# mLRS-E28-board01-v004.net
KiCad netlist of a schematic drawn in EAGLE
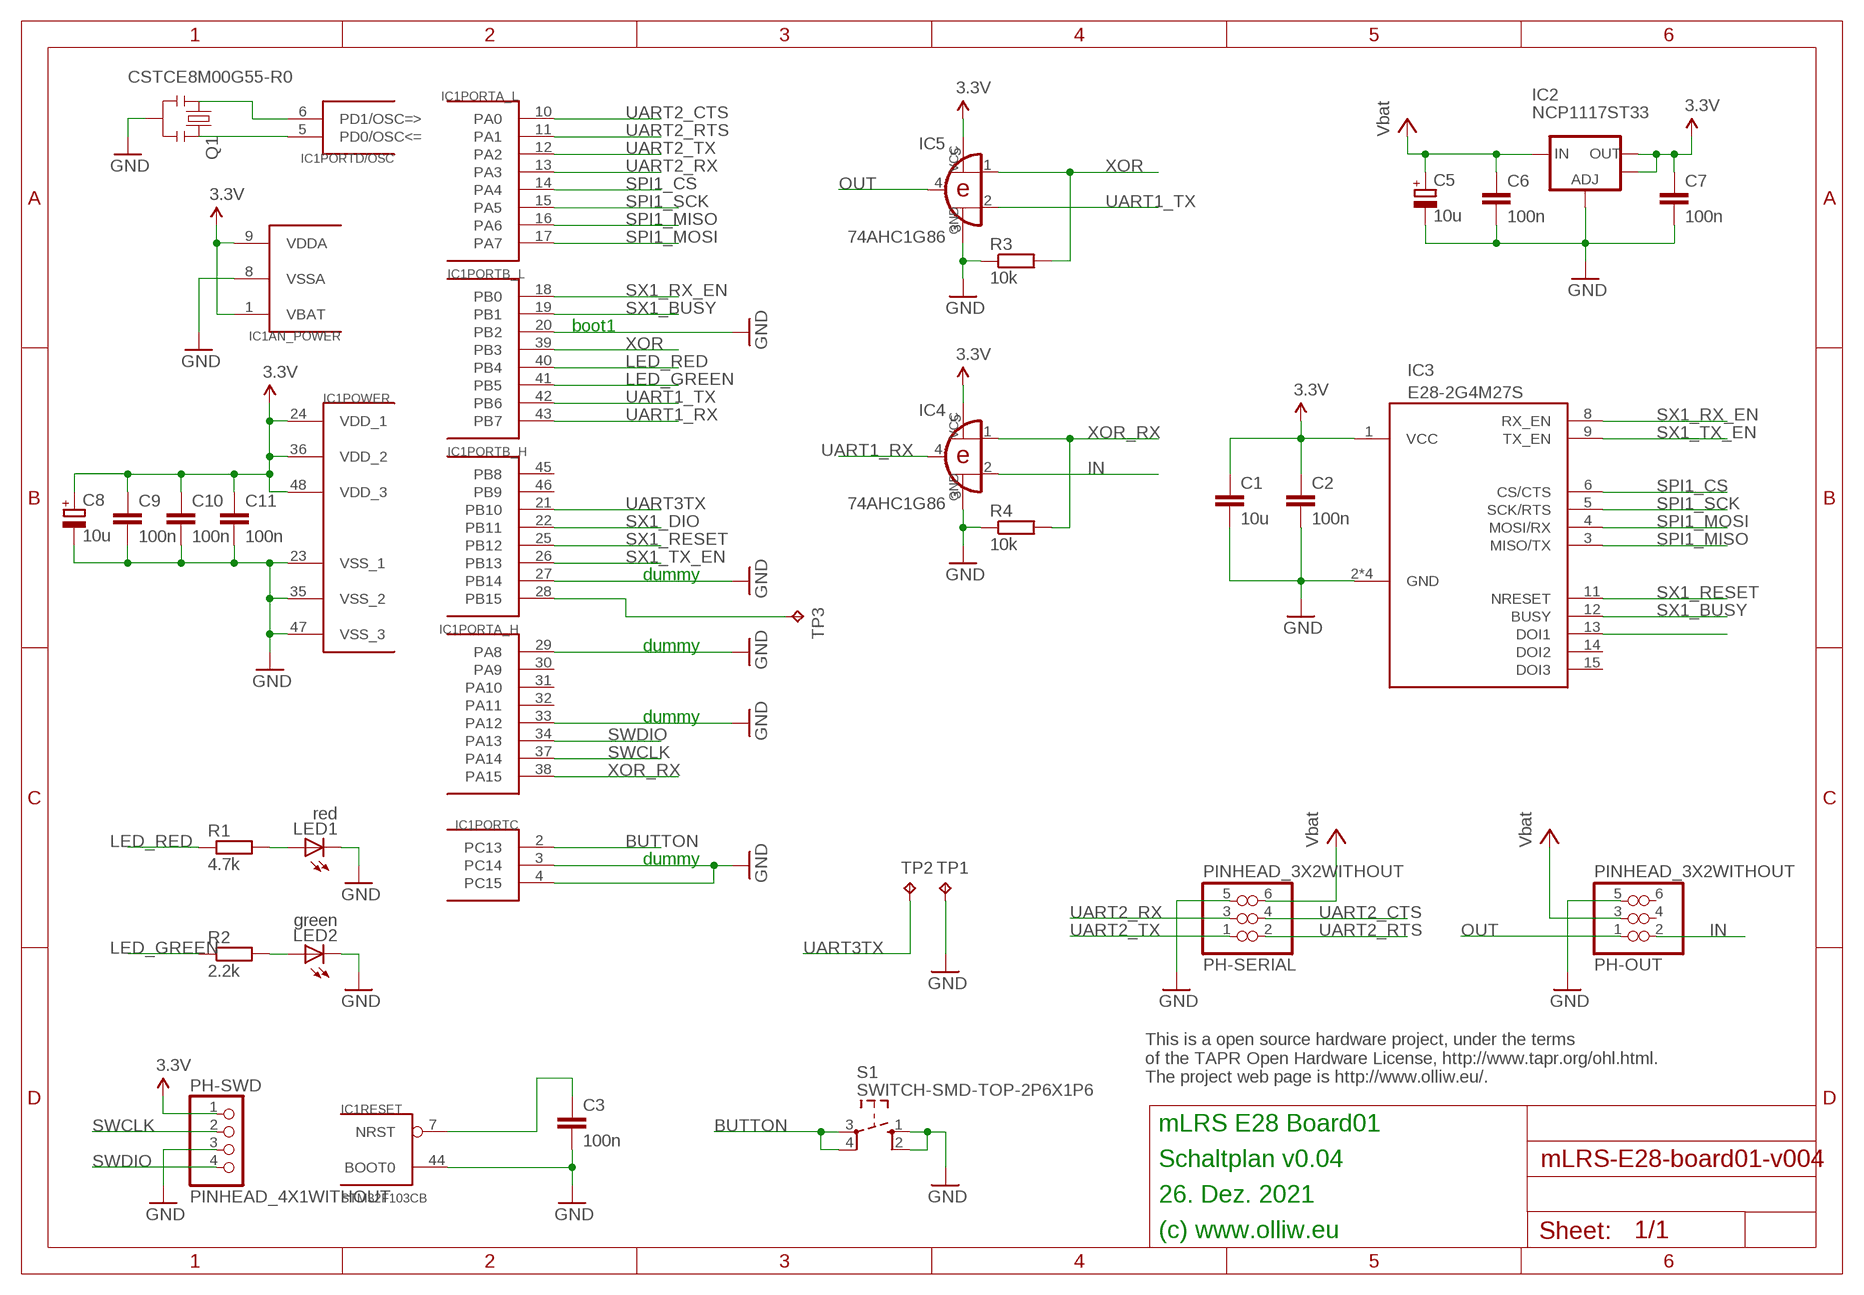
[diagram p0: schematic, sheet 1]

(export (version "E")
  (design (tool "Eeschema 10.0.6"))
  (components
    (comp (ref "C1")
      (value "10u")
      (footprint "eagle-import:C0603")
      (libsource (lib "eagle-import") (part "C-EUC0603"))
    )
    (comp (ref "C2")
      (value "100n")
      (footprint "eagle-import:C0402")
      (libsource (lib "eagle-import") (part "C-EUC0402"))
    )
    (comp (ref "C3")
      (value "100n")
      (footprint "eagle-import:C0603")
      (libsource (lib "eagle-import") (part "C-EUC0603"))
    )
    (comp (ref "C5")
      (value "10u")
      (footprint "eagle-import:SMC_A")
      (libsource (lib "eagle-import") (part "CPOL-EUSMCA"))
    )
    (comp (ref "C6")
      (value "100n")
      (footprint "eagle-import:C0603")
      (libsource (lib "eagle-import") (part "C-EUC0603"))
    )
    (comp (ref "C7")
      (value "100n")
      (footprint "eagle-import:C0603")
      (libsource (lib "eagle-import") (part "C-EUC0603"))
    )
    (comp (ref "C8")
      (value "10u")
      (footprint "eagle-import:SMC_A")
      (libsource (lib "eagle-import") (part "CPOL-EUSMCA"))
    )
    (comp (ref "C9")
      (value "100n")
      (footprint "eagle-import:C0603")
      (libsource (lib "eagle-import") (part "C-EUC0603"))
    )
    (comp (ref "C10")
      (value "100n")
      (footprint "eagle-import:C0603")
      (libsource (lib "eagle-import") (part "C-EUC0603"))
    )
    (comp (ref "C11")
      (value "100n")
      (footprint "eagle-import:C0603")
      (libsource (lib "eagle-import") (part "C-EUC0603"))
    )
    (comp (ref "IC1")
      (value "STM32F103CB")
      (footprint "eagle-import:TQFP48")
      (libsource (lib "eagle-import") (part "STM32F10XCXT6"))
    )
    (comp (ref "IC2")
      (value "NCP1117ST33")
      (footprint "eagle-import:SOT223")
      (libsource (lib "eagle-import") (part "V_REG_LM1117SOT223"))
    )
    (comp (ref "IC3")
      (value "E28-2G4M27S")
      (footprint "eagle-import:E28-2G4M27")
      (libsource (lib "eagle-import") (part "E28"))
    )
    (comp (ref "IC4")
      (value "74AHC1G86")
      (footprint "eagle-import:SOT23-5-VER1")
      (libsource (lib "eagle-import") (part "74AHC1G86"))
    )
    (comp (ref "IC5")
      (value "74AHC1G86")
      (footprint "eagle-import:SOT23-5-VER1")
      (libsource (lib "eagle-import") (part "74AHC1G86"))
    )
    (comp (ref "LED1")
      (value "red")
      (footprint "eagle-import:CHIPLED_0603")
      (libsource (lib "eagle-import") (part "LEDCHIPLED_0603"))
    )
    (comp (ref "LED2")
      (value "green")
      (footprint "eagle-import:CHIPLED_0603")
      (libsource (lib "eagle-import") (part "LEDCHIPLED_0603"))
    )
    (comp (ref "PH-OUT")
      (value "PINHEAD_3X2WITHOUT")
      (footprint "eagle-import:PINHEAD_3X2_WO")
      (libsource (lib "eagle-import") (part "PINHEAD_3X2WITHOUT"))
    )
    (comp (ref "PH-SERIAL")
      (value "PINHEAD_3X2WITHOUT")
      (footprint "eagle-import:PINHEAD_3X2_WO")
      (libsource (lib "eagle-import") (part "PINHEAD_3X2WITHOUT"))
    )
    (comp (ref "PH-SWD")
      (value "PINHEAD_4X1WITHOUT")
      (footprint "eagle-import:PINHEAD_4X1_WO")
      (libsource (lib "eagle-import") (part "PINHEAD_4X1WITHOUT"))
    )
    (comp (ref "Q1")
      (value "CSTCE8M00G55-R0")
      (footprint "eagle-import:RESONATOR-SMD")
      (libsource (lib "eagle-import") (part "RESONATORSMD"))
    )
    (comp (ref "R1")
      (value "4.7k")
      (footprint "eagle-import:R0402")
      (libsource (lib "eagle-import") (part "R-EU_R0402"))
    )
    (comp (ref "R2")
      (value "2.2k")
      (footprint "eagle-import:R0402")
      (libsource (lib "eagle-import") (part "R-EU_R0402"))
    )
    (comp (ref "R3")
      (value "10k")
      (footprint "eagle-import:R0402")
      (libsource (lib "eagle-import") (part "R-EU_R0402"))
    )
    (comp (ref "R4")
      (value "10k")
      (footprint "eagle-import:R0402")
      (libsource (lib "eagle-import") (part "R-EU_R0402"))
    )
    (comp (ref "S1")
      (value "SWITCH-SMD-TOP-2P6X1P6")
      (footprint "eagle-import:TACTILE-SWITCH-SMD-TOP-2P6X1X6")
      (libsource (lib "eagle-import") (part "SWITCH-SMD-TOP-2P6X1P6"))
    )
    (comp (ref "TP1")
      (value "TPB1,27")
      (footprint "eagle-import:B1,27")
      (libsource (lib "eagle-import") (part "TPB1,27"))
    )
    (comp (ref "TP2")
      (value "TPB1,27")
      (footprint "eagle-import:B1,27")
      (libsource (lib "eagle-import") (part "TPB1,27"))
    )
    (comp (ref "TP3")
      (value "TPTP08R")
      (footprint "eagle-import:TP08R")
      (libsource (lib "eagle-import") (part "TPTP08R"))
    )
  )
  (nets
    (net (code "1") (name "/BUTTON") (class "Default")
      (node (ref "IC1") (pin "2") (pinfunction "PC13_2") (pintype "bidirectional"))
      (node (ref "S1") (pin "3") (pinfunction "3_3") (pintype "passive"))
      (node (ref "S1") (pin "4") (pinfunction "4_4") (pintype "passive"))
    )
    (net (code "2") (name "/IN") (class "Default")
      (node (ref "IC4") (pin "2") (pinfunction "I1_2") (pintype "input"))
      (node (ref "PH-OUT") (pin "2") (pinfunction "2_2") (pintype "passive"))
    )
    (net (code "3") (name "/LED_GREEN") (class "Default")
      (node (ref "IC1") (pin "41") (pinfunction "PB5_41") (pintype "bidirectional"))
      (node (ref "R2") (pin "1") (pinfunction "1_1") (pintype "passive"))
    )
    (net (code "4") (name "/LED_RED") (class "Default")
      (node (ref "IC1") (pin "40") (pinfunction "PB4_40") (pintype "bidirectional"))
      (node (ref "R1") (pin "1") (pinfunction "1_1") (pintype "passive"))
    )
    (net (code "5") (name "/OUT") (class "Default")
      (node (ref "IC5") (pin "4") (pinfunction "O_4") (pintype "output"))
      (node (ref "PH-OUT") (pin "1") (pinfunction "1_1") (pintype "passive"))
    )
    (net (code "6") (name "/SPI1_CS") (class "Default")
      (node (ref "IC1") (pin "14") (pinfunction "PA4_14") (pintype "bidirectional"))
      (node (ref "IC3") (pin "6") (pinfunction "CS/CTS_6") (pintype "bidirectional"))
    )
    (net (code "7") (name "/SPI1_MISO") (class "Default")
      (node (ref "IC1") (pin "16") (pinfunction "PA6_16") (pintype "bidirectional"))
      (node (ref "IC3") (pin "3") (pinfunction "MISO/TX_3") (pintype "bidirectional"))
    )
    (net (code "8") (name "/SPI1_MOSI") (class "Default")
      (node (ref "IC1") (pin "17") (pinfunction "PA7_17") (pintype "bidirectional"))
      (node (ref "IC3") (pin "4") (pinfunction "MOSI/RX_4") (pintype "bidirectional"))
    )
    (net (code "9") (name "/SPI1_SCK") (class "Default")
      (node (ref "IC1") (pin "15") (pinfunction "PA5_15") (pintype "bidirectional"))
      (node (ref "IC3") (pin "5") (pinfunction "SCK/RTS_5") (pintype "bidirectional"))
    )
    (net (code "10") (name "/SWCLK") (class "Default")
      (node (ref "IC1") (pin "37") (pinfunction "PA14_37") (pintype "bidirectional"))
      (node (ref "PH-SWD") (pin "2") (pinfunction "2_2") (pintype "passive"))
    )
    (net (code "11") (name "/SWDIO") (class "Default")
      (node (ref "IC1") (pin "34") (pinfunction "PA13_34") (pintype "bidirectional"))
      (node (ref "PH-SWD") (pin "4") (pinfunction "4_4") (pintype "passive"))
    )
    (net (code "12") (name "/SX1_BUSY") (class "Default")
      (node (ref "IC1") (pin "19") (pinfunction "PB1_19") (pintype "bidirectional"))
      (node (ref "IC3") (pin "12") (pinfunction "BUSY_12") (pintype "bidirectional"))
    )
    (net (code "13") (name "/SX1_DIO") (class "Default")
      (node (ref "IC1") (pin "22") (pinfunction "PB11_22") (pintype "bidirectional"))
      (node (ref "IC3") (pin "13") (pinfunction "DOI1_13") (pintype "bidirectional"))
    )
    (net (code "14") (name "/SX1_RESET") (class "Default")
      (node (ref "IC1") (pin "25") (pinfunction "PB12_25") (pintype "bidirectional"))
      (node (ref "IC3") (pin "11") (pinfunction "NRESET_11") (pintype "input"))
    )
    (net (code "15") (name "/SX1_RX_EN") (class "Default")
      (node (ref "IC1") (pin "18") (pinfunction "PB0_18") (pintype "bidirectional"))
      (node (ref "IC3") (pin "8") (pinfunction "RX_EN_8") (pintype "bidirectional"))
    )
    (net (code "16") (name "/SX1_TX_EN") (class "Default")
      (node (ref "IC1") (pin "26") (pinfunction "PB13_26") (pintype "bidirectional"))
      (node (ref "IC3") (pin "9") (pinfunction "TX_EN_9") (pintype "bidirectional"))
    )
    (net (code "17") (name "/UART1_RX") (class "Default")
      (node (ref "IC1") (pin "43") (pinfunction "PB7_43") (pintype "bidirectional"))
      (node (ref "IC4") (pin "4") (pinfunction "O_4") (pintype "output"))
    )
    (net (code "18") (name "/UART1_TX") (class "Default")
      (node (ref "IC1") (pin "42") (pinfunction "PB6_42") (pintype "bidirectional"))
      (node (ref "IC5") (pin "2") (pinfunction "I1_2") (pintype "input"))
    )
    (net (code "19") (name "/UART2_CTS") (class "Default")
      (node (ref "IC1") (pin "10") (pinfunction "PA0_10") (pintype "bidirectional"))
      (node (ref "PH-SERIAL") (pin "4") (pinfunction "4_4") (pintype "passive"))
    )
    (net (code "20") (name "/UART2_RTS") (class "Default")
      (node (ref "IC1") (pin "11") (pinfunction "PA1_11") (pintype "bidirectional"))
      (node (ref "PH-SERIAL") (pin "2") (pinfunction "2_2") (pintype "passive"))
    )
    (net (code "21") (name "/UART2_RX") (class "Default")
      (node (ref "IC1") (pin "13") (pinfunction "PA3_13") (pintype "bidirectional"))
      (node (ref "PH-SERIAL") (pin "3") (pinfunction "3_3") (pintype "passive"))
    )
    (net (code "22") (name "/UART2_TX") (class "Default")
      (node (ref "IC1") (pin "12") (pinfunction "PA2_12") (pintype "bidirectional"))
      (node (ref "PH-SERIAL") (pin "1") (pinfunction "1_1") (pintype "passive"))
    )
    (net (code "23") (name "/UART3TX") (class "Default")
      (node (ref "IC1") (pin "21") (pinfunction "PB10_21") (pintype "bidirectional"))
      (node (ref "TP2") (pin "TP") (pinfunction "TP_TP") (pintype "input"))
    )
    (net (code "24") (name "/XOR") (class "Default")
      (node (ref "IC1") (pin "39") (pinfunction "PB3_39") (pintype "bidirectional"))
      (node (ref "IC5") (pin "1") (pinfunction "I0_1") (pintype "input"))
      (node (ref "R3") (pin "2") (pinfunction "2_2") (pintype "passive"))
    )
    (net (code "25") (name "/XOR_RX") (class "Default")
      (node (ref "IC1") (pin "38") (pinfunction "PA15_38") (pintype "bidirectional"))
      (node (ref "IC4") (pin "1") (pinfunction "I0_1") (pintype "input"))
      (node (ref "R4") (pin "2") (pinfunction "2_2") (pintype "passive"))
    )
    (net (code "26") (name "3.3V") (class "Default")
      (node (ref "C1") (pin "1") (pinfunction "1_1") (pintype "passive"))
      (node (ref "C10") (pin "1") (pinfunction "1_1") (pintype "passive"))
      (node (ref "C11") (pin "1") (pinfunction "1_1") (pintype "passive"))
      (node (ref "C2") (pin "1") (pinfunction "1_1") (pintype "passive"))
      (node (ref "C7") (pin "1") (pinfunction "1_1") (pintype "passive"))
      (node (ref "C8") (pin "+") (pinfunction "+_+") (pintype "passive"))
      (node (ref "C9") (pin "1") (pinfunction "1_1") (pintype "passive"))
      (node (ref "IC1") (pin "1") (pinfunction "VBAT_1") (pintype "power_in"))
      (node (ref "IC1") (pin "24") (pinfunction "VDD_1_24") (pintype "power_in"))
      (node (ref "IC1") (pin "36") (pinfunction "VDD_2_36") (pintype "power_in"))
      (node (ref "IC1") (pin "48") (pinfunction "VDD_3_48") (pintype "power_in"))
      (node (ref "IC1") (pin "9") (pinfunction "VDDA_9") (pintype "power_in"))
      (node (ref "IC2") (pin "2") (pinfunction "OUT_2") (pintype "output"))
      (node (ref "IC2") (pin "4") (pinfunction "OUT_4") (pintype "output"))
      (node (ref "IC3") (pin "1") (pinfunction "VCC_1") (pintype "power_in"))
      (node (ref "IC4") (pin "5") (pinfunction "VCC_5") (pintype "power_in"))
      (node (ref "IC5") (pin "5") (pinfunction "VCC_5") (pintype "power_in"))
      (node (ref "PH-SWD") (pin "1") (pinfunction "1_1") (pintype "passive"))
    )
    (net (code "27") (name "GND") (class "Default")
      (node (ref "C1") (pin "2") (pinfunction "2_2") (pintype "passive"))
      (node (ref "C10") (pin "2") (pinfunction "2_2") (pintype "passive"))
      (node (ref "C11") (pin "2") (pinfunction "2_2") (pintype "passive"))
      (node (ref "C2") (pin "2") (pinfunction "2_2") (pintype "passive"))
      (node (ref "C3") (pin "2") (pinfunction "2_2") (pintype "passive"))
      (node (ref "C5") (pin "-") (pinfunction "-_-") (pintype "passive"))
      (node (ref "C6") (pin "2") (pinfunction "2_2") (pintype "passive"))
      (node (ref "C7") (pin "2") (pinfunction "2_2") (pintype "passive"))
      (node (ref "C8") (pin "-") (pinfunction "-_-") (pintype "passive"))
      (node (ref "C9") (pin "2") (pinfunction "2_2") (pintype "passive"))
      (node (ref "IC1") (pin "20") (pinfunction "PB2_20") (pintype "bidirectional"))
      (node (ref "IC1") (pin "23") (pinfunction "VSS_1_23") (pintype "power_in"))
      (node (ref "IC1") (pin "27") (pinfunction "PB14_27") (pintype "bidirectional"))
      (node (ref "IC1") (pin "29") (pinfunction "PA8_29") (pintype "bidirectional"))
      (node (ref "IC1") (pin "3") (pinfunction "PC14_3") (pintype "bidirectional"))
      (node (ref "IC1") (pin "33") (pinfunction "PA12_33") (pintype "bidirectional"))
      (node (ref "IC1") (pin "35") (pinfunction "VSS_2_35") (pintype "power_in"))
      (node (ref "IC1") (pin "4") (pinfunction "PC15_4") (pintype "bidirectional"))
      (node (ref "IC1") (pin "44") (pinfunction "BOOT0_44") (pintype "input"))
      (node (ref "IC1") (pin "47") (pinfunction "VSS_3_47") (pintype "power_in"))
      (node (ref "IC1") (pin "8") (pinfunction "VSSA_8") (pintype "power_in"))
      (node (ref "IC2") (pin "1") (pinfunction "ADJ_1") (pintype "input"))
      (node (ref "IC3") (pin "10") (pinfunction "GND_10") (pintype "power_in"))
      (node (ref "IC3") (pin "16") (pinfunction "GND_16") (pintype "power_in"))
      (node (ref "IC3") (pin "2") (pinfunction "GND_2") (pintype "power_in"))
      (node (ref "IC3") (pin "7") (pinfunction "GND_7") (pintype "power_in"))
      (node (ref "IC4") (pin "3") (pinfunction "GND_3") (pintype "power_in"))
      (node (ref "IC5") (pin "3") (pinfunction "GND_3") (pintype "power_in"))
      (node (ref "LED1") (pin "C") (pinfunction "C_C") (pintype "passive"))
      (node (ref "LED2") (pin "C") (pinfunction "C_C") (pintype "passive"))
      (node (ref "PH-OUT") (pin "5") (pinfunction "5_5") (pintype "passive"))
      (node (ref "PH-SERIAL") (pin "5") (pinfunction "5_5") (pintype "passive"))
      (node (ref "PH-SWD") (pin "3") (pinfunction "3_3") (pintype "passive"))
      (node (ref "Q1") (pin "2") (pinfunction "2_2") (pintype "passive"))
      (node (ref "R3") (pin "1") (pinfunction "1_1") (pintype "passive"))
      (node (ref "R4") (pin "1") (pinfunction "1_1") (pintype "passive"))
      (node (ref "S1") (pin "1") (pinfunction "1_1") (pintype "passive"))
      (node (ref "S1") (pin "2") (pinfunction "2_2") (pintype "passive"))
      (node (ref "TP1") (pin "TP") (pinfunction "TP_TP") (pintype "input"))
    )
    (net (code "28") (name "Net-(IC1D-PB15)") (class "Default")
      (node (ref "IC1") (pin "28") (pinfunction "PB15_28") (pintype "bidirectional"))
      (node (ref "TP3") (pin "TP") (pinfunction "TP_TP") (pintype "input"))
    )
    (net (code "29") (name "Net-(IC1G-PD0{slash}OSC<=)") (class "Default")
      (node (ref "IC1") (pin "5") (pinfunction "PD0/OSC<=_5") (pintype "bidirectional"))
      (node (ref "Q1") (pin "3") (pinfunction "3_3") (pintype "passive"))
    )
    (net (code "30") (name "Net-(IC1G-PD1{slash}OSC=>)") (class "Default")
      (node (ref "IC1") (pin "6") (pinfunction "PD1/OSC=>_6") (pintype "bidirectional"))
      (node (ref "Q1") (pin "1") (pinfunction "1_1") (pintype "passive"))
    )
    (net (code "31") (name "Net-(IC1I-NRST)") (class "Default")
      (node (ref "C3") (pin "1") (pinfunction "1_1") (pintype "passive"))
      (node (ref "IC1") (pin "7") (pinfunction "NRST_7") (pintype "input"))
    )
    (net (code "32") (name "Net-(LED1-PadA)") (class "Default")
      (node (ref "LED1") (pin "A") (pinfunction "A_A") (pintype "passive"))
      (node (ref "R1") (pin "2") (pinfunction "2_2") (pintype "passive"))
    )
    (net (code "33") (name "Net-(LED2-PadA)") (class "Default")
      (node (ref "LED2") (pin "A") (pinfunction "A_A") (pintype "passive"))
      (node (ref "R2") (pin "2") (pinfunction "2_2") (pintype "passive"))
    )
    (net (code "34") (name "Vbat") (class "Default")
      (node (ref "C5") (pin "+") (pinfunction "+_+") (pintype "passive"))
      (node (ref "C6") (pin "1") (pinfunction "1_1") (pintype "passive"))
      (node (ref "IC2") (pin "3") (pinfunction "IN_3") (pintype "input"))
      (node (ref "PH-OUT") (pin "3") (pinfunction "3_3") (pintype "passive"))
      (node (ref "PH-SERIAL") (pin "6") (pinfunction "6_6") (pintype "passive"))
    )
    (net (code "35") (name "unconnected-(IC1B-PA9-Pad30)") (class "Default")
      (node (ref "IC1") (pin "30") (pinfunction "PA9_30") (pintype "bidirectional"))
    )
    (net (code "36") (name "unconnected-(IC1B-PA10-Pad31)") (class "Default")
      (node (ref "IC1") (pin "31") (pinfunction "PA10_31") (pintype "bidirectional"))
    )
    (net (code "37") (name "unconnected-(IC1B-PA11-Pad32)") (class "Default")
      (node (ref "IC1") (pin "32") (pinfunction "PA11_32") (pintype "bidirectional"))
    )
    (net (code "38") (name "unconnected-(IC1D-PB8-Pad45)") (class "Default")
      (node (ref "IC1") (pin "45") (pinfunction "PB8_45") (pintype "bidirectional"))
    )
    (net (code "39") (name "unconnected-(IC1D-PB9-Pad46)") (class "Default")
      (node (ref "IC1") (pin "46") (pinfunction "PB9_46") (pintype "bidirectional"))
    )
    (net (code "40") (name "unconnected-(IC3-DOI2-Pad14)") (class "Default")
      (node (ref "IC3") (pin "14") (pinfunction "DOI2_14") (pintype "bidirectional"))
    )
    (net (code "41") (name "unconnected-(IC3-DOI3-Pad15)") (class "Default")
      (node (ref "IC3") (pin "15") (pinfunction "DOI3_15") (pintype "bidirectional"))
    )
    (net (code "42") (name "unconnected-(PH-OUT-Pad4)") (class "Default")
      (node (ref "PH-OUT") (pin "4") (pinfunction "4_4") (pintype "passive"))
    )
    (net (code "43") (name "unconnected-(PH-OUT-Pad6)") (class "Default")
      (node (ref "PH-OUT") (pin "6") (pinfunction "6_6") (pintype "passive"))
    )
  )
)
